# Carriage_Board.net
KiCad netlist of a schematic drawn in EAGLE
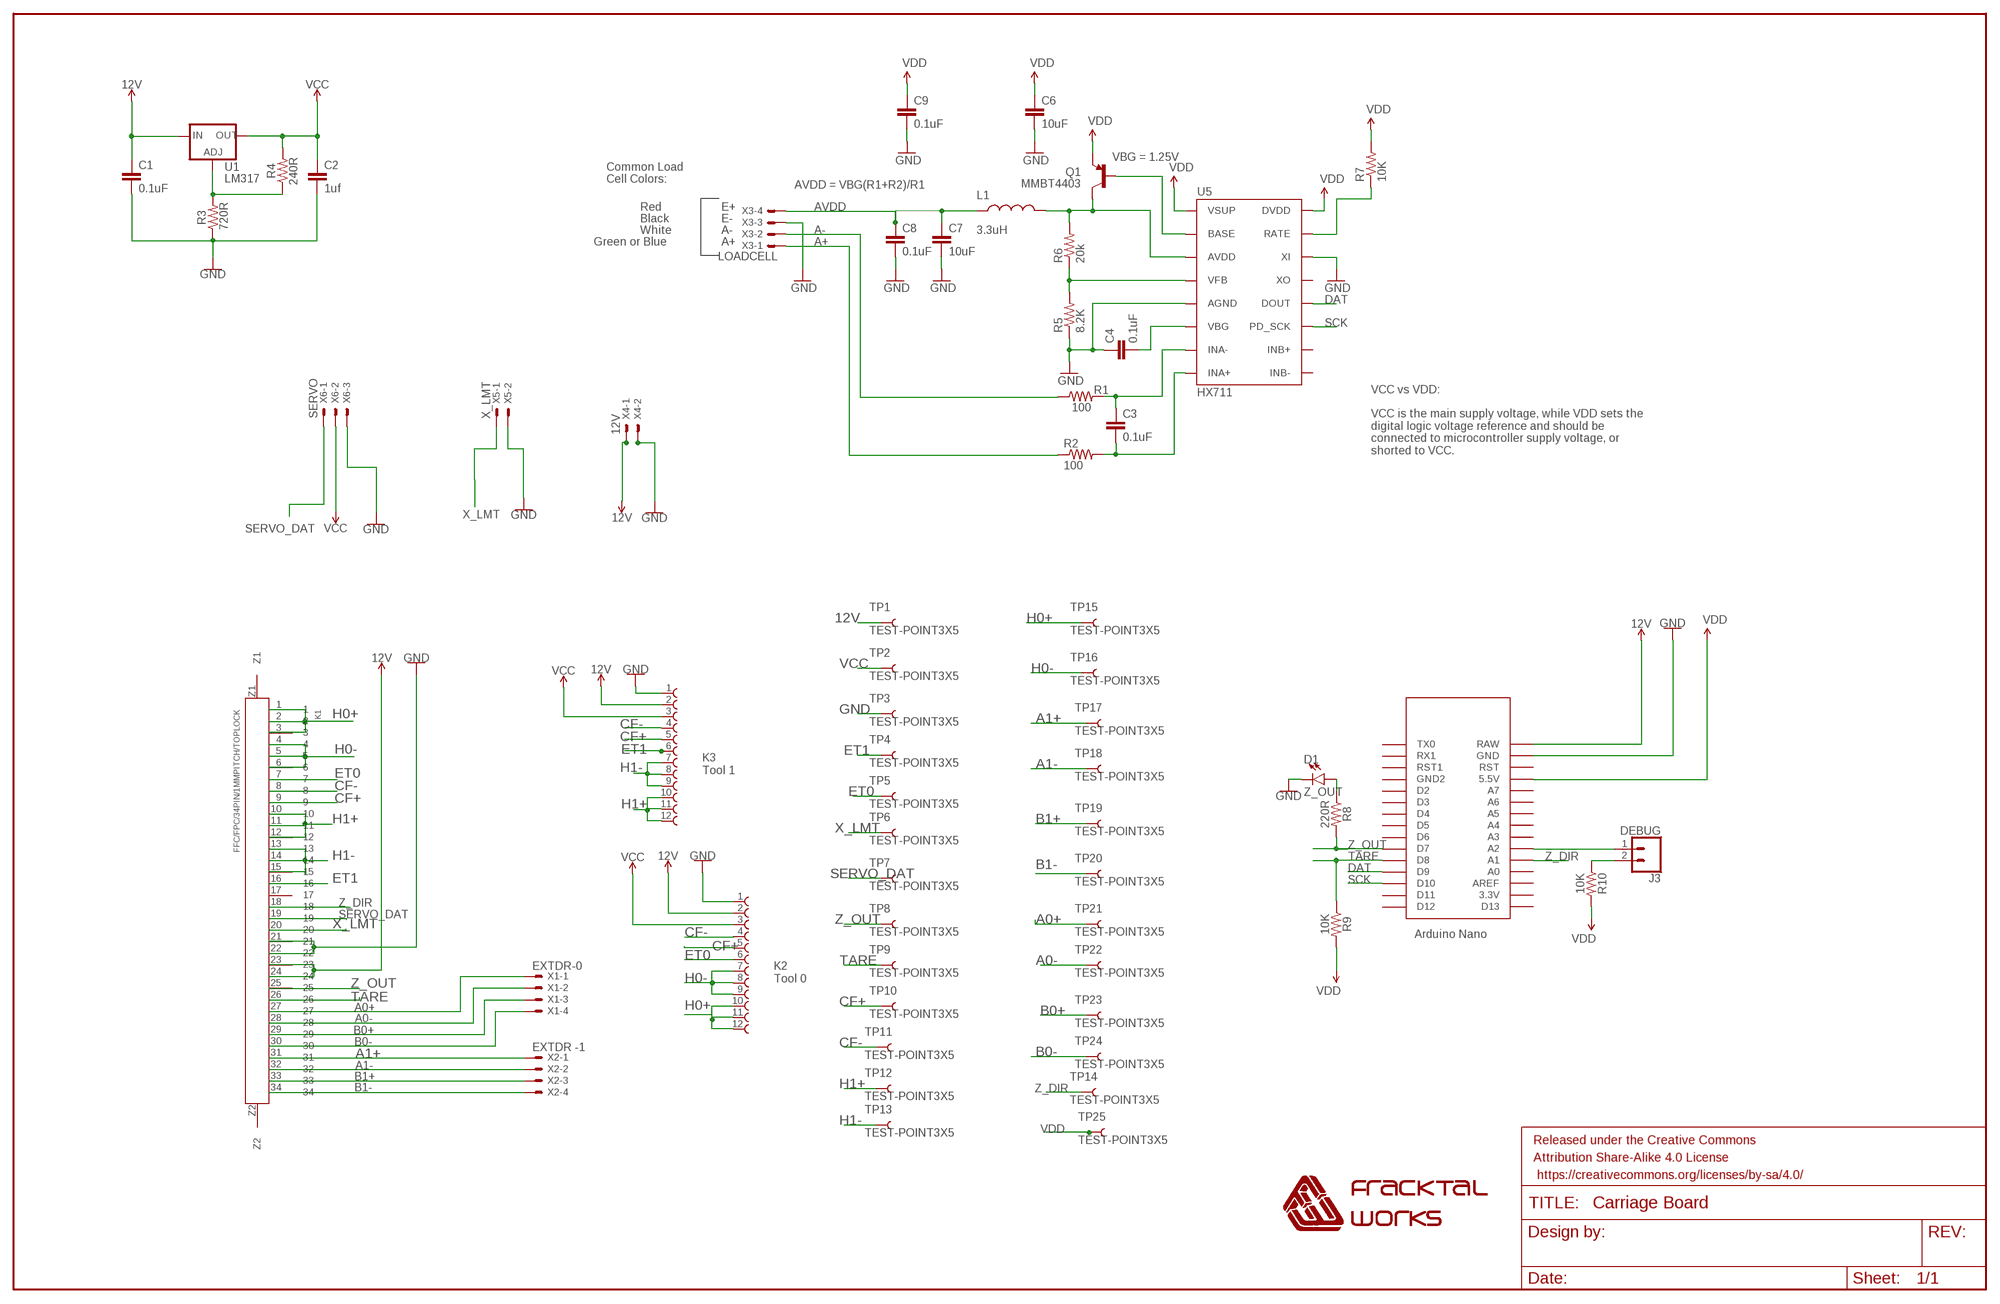
[diagram p0: schematic, sheet 1]

(export (version "E")
  (design (tool "Eeschema 10.0.6"))
  (components
    (comp (ref "C1")
      (value "0.1uF")
      (footprint "eagle-import:0603")
      (libsource (lib "eagle-import") (part "9.0PF-0603-50V-10%"))
    )
    (comp (ref "C2")
      (value "1uf")
      (footprint "eagle-import:0603")
      (libsource (lib "eagle-import") (part "9.0PF-0603-50V-10%"))
    )
    (comp (ref "C3")
      (value "0.1uF")
      (footprint "eagle-import:0603-CAP")
      (libsource (lib "eagle-import") (part "0.1UF-25V-5%(0603)"))
    )
    (comp (ref "C4")
      (value "0.1uF")
      (footprint "eagle-import:0603-CAP")
      (libsource (lib "eagle-import") (part "0.1UF-25V-5%(0603)"))
    )
    (comp (ref "C6")
      (value "10uF")
      (footprint "eagle-import:1210")
      (libsource (lib "eagle-import") (part "10UF50V20%(1210)"))
    )
    (comp (ref "C7")
      (value "10uF")
      (footprint "eagle-import:1210")
      (libsource (lib "eagle-import") (part "10UF50V20%(1210)"))
    )
    (comp (ref "C8")
      (value "0.1uF")
      (footprint "eagle-import:0603-CAP")
      (libsource (lib "eagle-import") (part "0.1UF-25V-5%(0603)"))
    )
    (comp (ref "C9")
      (value "0.1uF")
      (footprint "eagle-import:0603-CAP")
      (libsource (lib "eagle-import") (part "0.1UF-25V-5%(0603)"))
    )
    (comp (ref "D1")
      (value "Z_OUT")
      (footprint "eagle-import:LED_3MM")
      (libsource (lib "eagle-import") (part "LED3MM"))
    )
    (comp (ref "FRAME1")
      (value "FRAME-LEDGER")
      (footprint "eagle-import:CREATIVE_COMMONS")
      (libsource (lib "eagle-import") (part "FRAME-LEDGER"))
    )
    (comp (ref "J3")
      (value "DEBUG")
      (footprint "eagle-import:1X02")
      (libsource (lib "eagle-import") (part "CONN_02"))
    )
    (comp (ref "K1")
      (value "FFC/FPC/34PIN/1MMPITCH/TOPLOCK")
      (footprint "eagle-import:34PIN_1MMPITCH_FFC_FPC")
      (libsource (lib "eagle-import") (part "FFC/FPC/34PIN/1MMPITCH/TOPLOCK"))
    )
    (comp (ref "K2")
      (value "Tool 0")
      (footprint "eagle-import:68611214122")
      (libsource (lib "eagle-import") (part "68611214122"))
    )
    (comp (ref "K3")
      (value "Tool 1")
      (footprint "eagle-import:68611214122")
      (libsource (lib "eagle-import") (part "68611214122"))
    )
    (comp (ref "L1")
      (value "3.3uH")
      (footprint "eagle-import:0805")
      (libsource (lib "eagle-import") (part "INDUCTOR0805-IND"))
    )
    (comp (ref "Q1")
      (value "MMBT4403")
      (footprint "eagle-import:SOT23-3")
      (libsource (lib "eagle-import") (part "TRANSISTOR_PNPMMBT4403"))
    )
    (comp (ref "R1")
      (value "100")
      (footprint "eagle-import:0603-RES")
      (libsource (lib "eagle-import") (part "100OHM-1/10W-1%(0603)"))
    )
    (comp (ref "R2")
      (value "100")
      (footprint "eagle-import:0603-RES")
      (libsource (lib "eagle-import") (part "100OHM-1/10W-1%(0603)"))
    )
    (comp (ref "R3")
      (value "720R")
      (footprint "eagle-import:0603")
      (libsource (lib "eagle-import") (part "RESISTOR0603"))
    )
    (comp (ref "R4")
      (value "240R")
      (footprint "eagle-import:0603")
      (libsource (lib "eagle-import") (part "RESISTOR0603"))
    )
    (comp (ref "R5")
      (value "8.2K")
      (footprint "eagle-import:0603-RES")
      (libsource (lib "eagle-import") (part "8.2KOHM-1/10W-5%(0603)"))
    )
    (comp (ref "R6")
      (value "20k")
      (footprint "eagle-import:0603-RES")
      (libsource (lib "eagle-import") (part "20KOHM1/10W1%(0603)"))
    )
    (comp (ref "R7")
      (value "10K")
      (footprint "eagle-import:0603-RES")
      (libsource (lib "eagle-import") (part "10KOHM-1/10W-1%(0603)0603"))
    )
    (comp (ref "R8")
      (value "220R")
      (footprint "eagle-import:0603")
      (libsource (lib "eagle-import") (part "RESISTOR0603"))
    )
    (comp (ref "R9")
      (value "10K")
      (footprint "eagle-import:0603")
      (libsource (lib "eagle-import") (part "RESISTOR0603"))
    )
    (comp (ref "R10")
      (value "10K")
      (footprint "eagle-import:0603")
      (libsource (lib "eagle-import") (part "RESISTOR0603"))
    )
    (comp (ref "TP1")
      (value "TEST-POINT3X5")
      (footprint "eagle-import:PAD.03X.05")
      (libsource (lib "eagle-import") (part "TEST-POINT3X5"))
    )
    (comp (ref "TP2")
      (value "TEST-POINT3X5")
      (footprint "eagle-import:PAD.03X.05")
      (libsource (lib "eagle-import") (part "TEST-POINT3X5"))
    )
    (comp (ref "TP3")
      (value "TEST-POINT3X5")
      (footprint "eagle-import:PAD.03X.05")
      (libsource (lib "eagle-import") (part "TEST-POINT3X5"))
    )
    (comp (ref "TP4")
      (value "TEST-POINT3X5")
      (footprint "eagle-import:PAD.03X.05")
      (libsource (lib "eagle-import") (part "TEST-POINT3X5"))
    )
    (comp (ref "TP5")
      (value "TEST-POINT3X5")
      (footprint "eagle-import:PAD.03X.05")
      (libsource (lib "eagle-import") (part "TEST-POINT3X5"))
    )
    (comp (ref "TP6")
      (value "TEST-POINT3X5")
      (footprint "eagle-import:PAD.03X.05")
      (libsource (lib "eagle-import") (part "TEST-POINT3X5"))
    )
    (comp (ref "TP7")
      (value "TEST-POINT3X5")
      (footprint "eagle-import:PAD.03X.05")
      (libsource (lib "eagle-import") (part "TEST-POINT3X5"))
    )
    (comp (ref "TP8")
      (value "TEST-POINT3X5")
      (footprint "eagle-import:PAD.03X.05")
      (libsource (lib "eagle-import") (part "TEST-POINT3X5"))
    )
    (comp (ref "TP9")
      (value "TEST-POINT3X5")
      (footprint "eagle-import:PAD.03X.05")
      (libsource (lib "eagle-import") (part "TEST-POINT3X5"))
    )
    (comp (ref "TP10")
      (value "TEST-POINT3X5")
      (footprint "eagle-import:PAD.03X.05")
      (libsource (lib "eagle-import") (part "TEST-POINT3X5"))
    )
    (comp (ref "TP11")
      (value "TEST-POINT3X5")
      (footprint "eagle-import:PAD.03X.05")
      (libsource (lib "eagle-import") (part "TEST-POINT3X5"))
    )
    (comp (ref "TP12")
      (value "TEST-POINT3X5")
      (footprint "eagle-import:PAD.03X.05")
      (libsource (lib "eagle-import") (part "TEST-POINT3X5"))
    )
    (comp (ref "TP13")
      (value "TEST-POINT3X5")
      (footprint "eagle-import:PAD.03X.05")
      (libsource (lib "eagle-import") (part "TEST-POINT3X5"))
    )
    (comp (ref "TP14")
      (value "TEST-POINT3X5")
      (footprint "eagle-import:PAD.03X.05")
      (libsource (lib "eagle-import") (part "TEST-POINT3X5"))
    )
    (comp (ref "TP15")
      (value "TEST-POINT3X5")
      (footprint "eagle-import:PAD.03X.05")
      (libsource (lib "eagle-import") (part "TEST-POINT3X5"))
    )
    (comp (ref "TP16")
      (value "TEST-POINT3X5")
      (footprint "eagle-import:PAD.03X.05")
      (libsource (lib "eagle-import") (part "TEST-POINT3X5"))
    )
    (comp (ref "TP17")
      (value "TEST-POINT3X5")
      (footprint "eagle-import:PAD.03X.05")
      (libsource (lib "eagle-import") (part "TEST-POINT3X5"))
    )
    (comp (ref "TP18")
      (value "TEST-POINT3X5")
      (footprint "eagle-import:PAD.03X.05")
      (libsource (lib "eagle-import") (part "TEST-POINT3X5"))
    )
    (comp (ref "TP19")
      (value "TEST-POINT3X5")
      (footprint "eagle-import:PAD.03X.05")
      (libsource (lib "eagle-import") (part "TEST-POINT3X5"))
    )
    (comp (ref "TP20")
      (value "TEST-POINT3X5")
      (footprint "eagle-import:PAD.03X.05")
      (libsource (lib "eagle-import") (part "TEST-POINT3X5"))
    )
    (comp (ref "TP21")
      (value "TEST-POINT3X5")
      (footprint "eagle-import:PAD.03X.05")
      (libsource (lib "eagle-import") (part "TEST-POINT3X5"))
    )
    (comp (ref "TP22")
      (value "TEST-POINT3X5")
      (footprint "eagle-import:PAD.03X.05")
      (libsource (lib "eagle-import") (part "TEST-POINT3X5"))
    )
    (comp (ref "TP23")
      (value "TEST-POINT3X5")
      (footprint "eagle-import:PAD.03X.05")
      (libsource (lib "eagle-import") (part "TEST-POINT3X5"))
    )
    (comp (ref "TP24")
      (value "TEST-POINT3X5")
      (footprint "eagle-import:PAD.03X.05")
      (libsource (lib "eagle-import") (part "TEST-POINT3X5"))
    )
    (comp (ref "TP25")
      (value "TEST-POINT3X5")
      (footprint "eagle-import:PAD.03X.05")
      (libsource (lib "eagle-import") (part "TEST-POINT3X5"))
    )
    (comp (ref "U$1")
      (value "NANO")
      (footprint "eagle-import:NANO")
      (libsource (lib "eagle-import") (part "NANO"))
    )
    (comp (ref "U$2")
      (value "FWLOGO")
      (footprint "eagle-import:FWLOGO")
      (libsource (lib "eagle-import") (part "FWLOGO"))
    )
    (comp (ref "U1")
      (value "LM317")
      (footprint "eagle-import:SOT223")
      (libsource (lib "eagle-import") (part "V_REG_317SMD"))
    )
    (comp (ref "U5")
      (value "HX711")
      (footprint "eagle-import:SO16")
      (libsource (lib "eagle-import") (part "HX711HX711"))
    )
    (comp (ref "X1")
      (value "EXTDR-0")
      (footprint "eagle-import:JST-XH-04-PACKAGE-LONG-PAD")
      (libsource (lib "eagle-import") (part "JST-XH-04-PIN-LONG-PAD"))
    )
    (comp (ref "X2")
      (value "EXTDR -1")
      (footprint "eagle-import:JST-XH-04-PACKAGE-LONG-PAD")
      (libsource (lib "eagle-import") (part "JST-XH-04-PIN-LONG-PAD"))
    )
    (comp (ref "X3")
      (value "LOADCELL")
      (footprint "eagle-import:JST-XH-04-PACKAGE-LONG-PAD")
      (libsource (lib "eagle-import") (part "JST-XH-04-PIN-LONG-PAD"))
    )
    (comp (ref "X4")
      (value "12V")
      (footprint "eagle-import:JST-XH-02-PACKAGE-LONG-PAD")
      (libsource (lib "eagle-import") (part "JST-XH-02-PIN-LONG-PAD"))
    )
    (comp (ref "X5")
      (value "X_LMT")
      (footprint "eagle-import:JST-XH-02-PACKAGE-LONG-PAD")
      (libsource (lib "eagle-import") (part "JST-XH-02-PIN-LONG-PAD"))
    )
    (comp (ref "X6")
      (value "SERVO")
      (footprint "eagle-import:JST-XH-03-PACKAGE-LONG-PAD")
      (libsource (lib "eagle-import") (part "JST-XH-03-PIN-LONG-PAD"))
    )
  )
  (nets
    (net (code "1") (name "/A+") (class "Default")
      (node (ref "R2") (pin "1") (pinfunction "1_1") (pintype "passive"))
      (node (ref "X3") (pin "1") (pinfunction "S_1") (pintype "passive"))
    )
    (net (code "2") (name "/A-") (class "Default")
      (node (ref "R1") (pin "1") (pinfunction "1_1") (pintype "passive"))
      (node (ref "X3") (pin "2") (pinfunction "S_2") (pintype "passive"))
    )
    (net (code "3") (name "/A0+") (class "Default")
      (node (ref "K1") (pin "27") (pinfunction "27_27") (pintype "bidirectional"))
      (node (ref "TP21") (pin "P$1") (pinfunction "1_P$1") (pintype "bidirectional"))
      (node (ref "X1") (pin "1") (pinfunction "S_1") (pintype "passive"))
    )
    (net (code "4") (name "/A0-") (class "Default")
      (node (ref "K1") (pin "28") (pinfunction "28_28") (pintype "bidirectional"))
      (node (ref "TP22") (pin "P$1") (pinfunction "1_P$1") (pintype "bidirectional"))
      (node (ref "X1") (pin "2") (pinfunction "S_2") (pintype "passive"))
    )
    (net (code "5") (name "/A1+") (class "Default")
      (node (ref "K1") (pin "31") (pinfunction "31_31") (pintype "bidirectional"))
      (node (ref "TP17") (pin "P$1") (pinfunction "1_P$1") (pintype "bidirectional"))
      (node (ref "X2") (pin "1") (pinfunction "S_1") (pintype "passive"))
    )
    (net (code "6") (name "/A1-") (class "Default")
      (node (ref "K1") (pin "32") (pinfunction "32_32") (pintype "bidirectional"))
      (node (ref "TP18") (pin "P$1") (pinfunction "1_P$1") (pintype "bidirectional"))
      (node (ref "X2") (pin "2") (pinfunction "S_2") (pintype "passive"))
    )
    (net (code "7") (name "/AVDD") (class "Default")
      (node (ref "C7") (pin "1") (pinfunction "1_1") (pintype "passive"))
      (node (ref "C8") (pin "1") (pinfunction "1_1") (pintype "passive"))
      (node (ref "L1") (pin "1") (pinfunction "1_1") (pintype "passive"))
      (node (ref "X3") (pin "4") (pinfunction "S_4") (pintype "passive"))
    )
    (net (code "8") (name "/B0+") (class "Default")
      (node (ref "K1") (pin "29") (pinfunction "29_29") (pintype "bidirectional"))
      (node (ref "TP23") (pin "P$1") (pinfunction "1_P$1") (pintype "bidirectional"))
      (node (ref "X1") (pin "3") (pinfunction "S_3") (pintype "passive"))
    )
    (net (code "9") (name "/B0-") (class "Default")
      (node (ref "K1") (pin "30") (pinfunction "30_30") (pintype "bidirectional"))
      (node (ref "TP24") (pin "P$1") (pinfunction "1_P$1") (pintype "bidirectional"))
      (node (ref "X1") (pin "4") (pinfunction "S_4") (pintype "passive"))
    )
    (net (code "10") (name "/B1+") (class "Default")
      (node (ref "K1") (pin "33") (pinfunction "33_33") (pintype "bidirectional"))
      (node (ref "TP19") (pin "P$1") (pinfunction "1_P$1") (pintype "bidirectional"))
      (node (ref "X2") (pin "3") (pinfunction "S_3") (pintype "passive"))
    )
    (net (code "11") (name "/B1-") (class "Default")
      (node (ref "K1") (pin "34") (pinfunction "34_34") (pintype "bidirectional"))
      (node (ref "TP20") (pin "P$1") (pinfunction "1_P$1") (pintype "bidirectional"))
      (node (ref "X2") (pin "4") (pinfunction "S_4") (pintype "passive"))
    )
    (net (code "12") (name "/CF+") (class "Default")
      (node (ref "K1") (pin "9") (pinfunction "9_9") (pintype "bidirectional"))
      (node (ref "K2") (pin "5") (pinfunction "5_5") (pintype "passive"))
      (node (ref "K3") (pin "5") (pinfunction "5_5") (pintype "passive"))
      (node (ref "TP10") (pin "P$1") (pinfunction "1_P$1") (pintype "bidirectional"))
    )
    (net (code "13") (name "/CF-") (class "Default")
      (node (ref "K1") (pin "8") (pinfunction "8_8") (pintype "bidirectional"))
      (node (ref "K2") (pin "4") (pinfunction "4_4") (pintype "passive"))
      (node (ref "K3") (pin "4") (pinfunction "4_4") (pintype "passive"))
      (node (ref "TP11") (pin "P$1") (pinfunction "1_P$1") (pintype "bidirectional"))
    )
    (net (code "14") (name "/DAT") (class "Default")
      (node (ref "U$1") (pin "D9") (pinfunction "D9_D9") (pintype "bidirectional"))
      (node (ref "U5") (pin "12") (pinfunction "DOUT_12") (pintype "bidirectional"))
    )
    (net (code "15") (name "/ET0") (class "Default")
      (node (ref "K1") (pin "7") (pinfunction "7_7") (pintype "bidirectional"))
      (node (ref "K2") (pin "6") (pinfunction "6_6") (pintype "passive"))
      (node (ref "TP5") (pin "P$1") (pinfunction "1_P$1") (pintype "bidirectional"))
    )
    (net (code "16") (name "/ET1") (class "Default")
      (node (ref "K1") (pin "16") (pinfunction "16_16") (pintype "bidirectional"))
      (node (ref "K3") (pin "6") (pinfunction "6_6") (pintype "passive"))
      (node (ref "TP4") (pin "P$1") (pinfunction "1_P$1") (pintype "bidirectional"))
    )
    (net (code "17") (name "/H0+") (class "Default")
      (node (ref "K1") (pin "1") (pinfunction "1_1") (pintype "bidirectional"))
      (node (ref "K1") (pin "2") (pinfunction "2_2") (pintype "bidirectional"))
      (node (ref "K1") (pin "3") (pinfunction "3_3") (pintype "bidirectional"))
      (node (ref "K2") (pin "10") (pinfunction "10_10") (pintype "passive"))
      (node (ref "K2") (pin "11") (pinfunction "11_11") (pintype "passive"))
      (node (ref "K2") (pin "12") (pinfunction "12_12") (pintype "passive"))
      (node (ref "TP15") (pin "P$1") (pinfunction "1_P$1") (pintype "bidirectional"))
    )
    (net (code "18") (name "/H0-") (class "Default")
      (node (ref "K1") (pin "4") (pinfunction "4_4") (pintype "bidirectional"))
      (node (ref "K1") (pin "5") (pinfunction "5_5") (pintype "bidirectional"))
      (node (ref "K1") (pin "6") (pinfunction "6_6") (pintype "bidirectional"))
      (node (ref "K2") (pin "7") (pinfunction "7_7") (pintype "passive"))
      (node (ref "K2") (pin "8") (pinfunction "8_8") (pintype "passive"))
      (node (ref "K2") (pin "9") (pinfunction "9_9") (pintype "passive"))
      (node (ref "TP16") (pin "P$1") (pinfunction "1_P$1") (pintype "bidirectional"))
    )
    (net (code "19") (name "/H1+") (class "Default")
      (node (ref "K1") (pin "10") (pinfunction "10_10") (pintype "bidirectional"))
      (node (ref "K1") (pin "11") (pinfunction "11_11") (pintype "bidirectional"))
      (node (ref "K1") (pin "12") (pinfunction "12_12") (pintype "bidirectional"))
      (node (ref "K3") (pin "10") (pinfunction "10_10") (pintype "passive"))
      (node (ref "K3") (pin "11") (pinfunction "11_11") (pintype "passive"))
      (node (ref "K3") (pin "12") (pinfunction "12_12") (pintype "passive"))
      (node (ref "TP12") (pin "P$1") (pinfunction "1_P$1") (pintype "bidirectional"))
    )
    (net (code "20") (name "/H1-") (class "Default")
      (node (ref "K1") (pin "13") (pinfunction "13_13") (pintype "bidirectional"))
      (node (ref "K1") (pin "14") (pinfunction "14_14") (pintype "bidirectional"))
      (node (ref "K1") (pin "15") (pinfunction "15_15") (pintype "bidirectional"))
      (node (ref "K3") (pin "7") (pinfunction "7_7") (pintype "passive"))
      (node (ref "K3") (pin "8") (pinfunction "8_8") (pintype "passive"))
      (node (ref "K3") (pin "9") (pinfunction "9_9") (pintype "passive"))
      (node (ref "TP13") (pin "P$1") (pinfunction "1_P$1") (pintype "bidirectional"))
    )
    (net (code "21") (name "/SCK") (class "Default")
      (node (ref "U$1") (pin "D10") (pinfunction "D10_D10") (pintype "bidirectional"))
      (node (ref "U5") (pin "11") (pinfunction "PD_SCK_11") (pintype "bidirectional"))
    )
    (net (code "22") (name "/SERVO_DAT") (class "Default")
      (node (ref "K1") (pin "19") (pinfunction "19_19") (pintype "bidirectional"))
      (node (ref "TP7") (pin "P$1") (pinfunction "1_P$1") (pintype "bidirectional"))
      (node (ref "X6") (pin "1") (pinfunction "S_1") (pintype "passive"))
    )
    (net (code "23") (name "/TARE") (class "Default")
      (node (ref "K1") (pin "26") (pinfunction "26_26") (pintype "bidirectional"))
      (node (ref "R9") (pin "1") (pinfunction "1_1") (pintype "passive"))
      (node (ref "TP9") (pin "P$1") (pinfunction "1_P$1") (pintype "bidirectional"))
      (node (ref "U$1") (pin "D8") (pinfunction "D8_D8") (pintype "bidirectional"))
    )
    (net (code "24") (name "/X_LMT") (class "Default")
      (node (ref "K1") (pin "20") (pinfunction "20_20") (pintype "bidirectional"))
      (node (ref "TP6") (pin "P$1") (pinfunction "1_P$1") (pintype "bidirectional"))
      (node (ref "X5") (pin "1") (pinfunction "S_1") (pintype "passive"))
    )
    (net (code "25") (name "/Z_DIR") (class "Default")
      (node (ref "K1") (pin "18") (pinfunction "18_18") (pintype "bidirectional"))
      (node (ref "TP14") (pin "P$1") (pinfunction "1_P$1") (pintype "bidirectional"))
      (node (ref "U$1") (pin "A1") (pinfunction "A1_A1") (pintype "bidirectional"))
    )
    (net (code "26") (name "/Z_OUT") (class "Default")
      (node (ref "K1") (pin "25") (pinfunction "25_25") (pintype "bidirectional"))
      (node (ref "R8") (pin "2") (pinfunction "2_2") (pintype "passive"))
      (node (ref "TP8") (pin "P$1") (pinfunction "1_P$1") (pintype "bidirectional"))
      (node (ref "U$1") (pin "D7") (pinfunction "D7_D7") (pintype "bidirectional"))
    )
    (net (code "27") (name "12V") (class "Default")
      (node (ref "C1") (pin "1") (pinfunction "1_1") (pintype "passive"))
      (node (ref "K1") (pin "23") (pinfunction "23_23") (pintype "bidirectional"))
      (node (ref "K1") (pin "24") (pinfunction "24_24") (pintype "bidirectional"))
      (node (ref "K2") (pin "2") (pinfunction "2_2") (pintype "passive"))
      (node (ref "K3") (pin "2") (pinfunction "2_2") (pintype "passive"))
      (node (ref "TP1") (pin "P$1") (pinfunction "1_P$1") (pintype "bidirectional"))
      (node (ref "U$1") (pin "RAW") (pinfunction "RAW_RAW") (pintype "bidirectional"))
      (node (ref "U1") (pin "3") (pinfunction "IN_3") (pintype "input"))
      (node (ref "X4") (pin "1") (pinfunction "S_1") (pintype "passive"))
    )
    (net (code "28") (name "GND") (class "Default")
      (node (ref "C1") (pin "2") (pinfunction "2_2") (pintype "passive"))
      (node (ref "C2") (pin "2") (pinfunction "2_2") (pintype "passive"))
      (node (ref "C4") (pin "1") (pinfunction "1_1") (pintype "passive"))
      (node (ref "C6") (pin "2") (pinfunction "2_2") (pintype "passive"))
      (node (ref "C7") (pin "2") (pinfunction "2_2") (pintype "passive"))
      (node (ref "C8") (pin "2") (pinfunction "2_2") (pintype "passive"))
      (node (ref "C9") (pin "2") (pinfunction "2_2") (pintype "passive"))
      (node (ref "D1") (pin "K") (pinfunction "C_K") (pintype "passive"))
      (node (ref "K1") (pin "21") (pinfunction "21_21") (pintype "bidirectional"))
      (node (ref "K1") (pin "22") (pinfunction "22_22") (pintype "bidirectional"))
      (node (ref "K2") (pin "1") (pinfunction "1_1") (pintype "passive"))
      (node (ref "K3") (pin "1") (pinfunction "1_1") (pintype "passive"))
      (node (ref "R3") (pin "1") (pinfunction "1_1") (pintype "passive"))
      (node (ref "R5") (pin "1") (pinfunction "1_1") (pintype "passive"))
      (node (ref "TP3") (pin "P$1") (pinfunction "1_P$1") (pintype "bidirectional"))
      (node (ref "U$1") (pin "GND") (pinfunction "GND_GND") (pintype "bidirectional"))
      (node (ref "U5") (pin "14") (pinfunction "XI_14") (pintype "bidirectional"))
      (node (ref "U5") (pin "5") (pinfunction "AGND_5") (pintype "bidirectional"))
      (node (ref "X3") (pin "3") (pinfunction "S_3") (pintype "passive"))
      (node (ref "X4") (pin "2") (pinfunction "S_2") (pintype "passive"))
      (node (ref "X5") (pin "2") (pinfunction "S_2") (pintype "passive"))
      (node (ref "X6") (pin "3") (pinfunction "S_3") (pintype "passive"))
    )
    (net (code "29") (name "Net-(D1-PadA)") (class "Default")
      (node (ref "D1") (pin "A") (pinfunction "A_A") (pintype "passive"))
      (node (ref "R8") (pin "1") (pinfunction "1_1") (pintype "passive"))
    )
    (net (code "30") (name "Net-(J3-Pad1)") (class "Default")
      (node (ref "J3") (pin "1") (pinfunction "1_1") (pintype "passive"))
      (node (ref "U$1") (pin "A2") (pinfunction "A2_A2") (pintype "bidirectional"))
    )
    (net (code "31") (name "Net-(J3-Pad2)") (class "Default")
      (node (ref "J3") (pin "2") (pinfunction "2_2") (pintype "passive"))
      (node (ref "R10") (pin "1") (pinfunction "1_1") (pintype "passive"))
    )
    (net (code "32") (name "Net-(Q1-B)") (class "Default")
      (node (ref "Q1") (pin "1") (pinfunction "B_1") (pintype "passive"))
      (node (ref "U5") (pin "2") (pinfunction "BASE_2") (pintype "bidirectional"))
    )
    (net (code "33") (name "Net-(Q1-C)") (class "Default")
      (node (ref "L1") (pin "2") (pinfunction "2_2") (pintype "passive"))
      (node (ref "Q1") (pin "3") (pinfunction "C_3") (pintype "passive"))
      (node (ref "R6") (pin "2") (pinfunction "2_2") (pintype "passive"))
      (node (ref "U5") (pin "3") (pinfunction "AVDD_3") (pintype "bidirectional"))
    )
    (net (code "34") (name "Net-(U1-ADJ)") (class "Default")
      (node (ref "R3") (pin "2") (pinfunction "2_2") (pintype "passive"))
      (node (ref "R4") (pin "1") (pinfunction "1_1") (pintype "passive"))
      (node (ref "U1") (pin "1") (pinfunction "ADJ_1") (pintype "input"))
    )
    (net (code "35") (name "Net-(U5-INA+)") (class "Default")
      (node (ref "C3") (pin "2") (pinfunction "2_2") (pintype "passive"))
      (node (ref "R2") (pin "2") (pinfunction "2_2") (pintype "passive"))
      (node (ref "U5") (pin "8") (pinfunction "INA+_8") (pintype "bidirectional"))
    )
    (net (code "36") (name "Net-(U5-INA-)") (class "Default")
      (node (ref "C3") (pin "1") (pinfunction "1_1") (pintype "passive"))
      (node (ref "R1") (pin "2") (pinfunction "2_2") (pintype "passive"))
      (node (ref "U5") (pin "7") (pinfunction "INA-_7") (pintype "bidirectional"))
    )
    (net (code "37") (name "Net-(U5-RATE)") (class "Default")
      (node (ref "R7") (pin "1") (pinfunction "1_1") (pintype "passive"))
      (node (ref "U5") (pin "15") (pinfunction "RATE_15") (pintype "bidirectional"))
    )
    (net (code "38") (name "Net-(U5-VBG)") (class "Default")
      (node (ref "C4") (pin "2") (pinfunction "2_2") (pintype "passive"))
      (node (ref "U5") (pin "6") (pinfunction "VBG_6") (pintype "bidirectional"))
    )
    (net (code "39") (name "Net-(U5-VFB)") (class "Default")
      (node (ref "R5") (pin "2") (pinfunction "2_2") (pintype "passive"))
      (node (ref "R6") (pin "1") (pinfunction "1_1") (pintype "passive"))
      (node (ref "U5") (pin "4") (pinfunction "VFB_4") (pintype "bidirectional"))
    )
    (net (code "40") (name "VCC") (class "Default")
      (node (ref "C2") (pin "1") (pinfunction "1_1") (pintype "passive"))
      (node (ref "K2") (pin "3") (pinfunction "3_3") (pintype "passive"))
      (node (ref "K3") (pin "3") (pinfunction "3_3") (pintype "passive"))
      (node (ref "R4") (pin "2") (pinfunction "2_2") (pintype "passive"))
      (node (ref "TP2") (pin "P$1") (pinfunction "1_P$1") (pintype "bidirectional"))
      (node (ref "U1") (pin "2") (pinfunction "OUT_2") (pintype "output"))
      (node (ref "X6") (pin "2") (pinfunction "S_2") (pintype "passive"))
    )
    (net (code "41") (name "VDD") (class "Default")
      (node (ref "C6") (pin "1") (pinfunction "1_1") (pintype "passive"))
      (node (ref "C9") (pin "1") (pinfunction "1_1") (pintype "passive"))
      (node (ref "Q1") (pin "2") (pinfunction "E_2") (pintype "passive"))
      (node (ref "R10") (pin "2") (pinfunction "2_2") (pintype "passive"))
      (node (ref "R7") (pin "2") (pinfunction "2_2") (pintype "passive"))
      (node (ref "R9") (pin "2") (pinfunction "2_2") (pintype "passive"))
      (node (ref "TP25") (pin "P$1") (pinfunction "1_P$1") (pintype "bidirectional"))
      (node (ref "U$1") (pin "5V") (pinfunction "5.5V_5V") (pintype "bidirectional"))
      (node (ref "U5") (pin "1") (pinfunction "VSUP_1") (pintype "bidirectional"))
      (node (ref "U5") (pin "16") (pinfunction "DVDD_16") (pintype "bidirectional"))
    )
    (net (code "42") (name "unconnected-(K1-Pad17)") (class "Default")
      (node (ref "K1") (pin "17") (pinfunction "17_17") (pintype "bidirectional"))
    )
    (net (code "43") (name "unconnected-(K1-PadZ1)") (class "Default")
      (node (ref "K1") (pin "Z1") (pinfunction "Z1_Z1") (pintype "bidirectional"))
    )
    (net (code "44") (name "unconnected-(K1-PadZ2)") (class "Default")
      (node (ref "K1") (pin "Z2") (pinfunction "Z2_Z2") (pintype "bidirectional"))
    )
    (net (code "45") (name "unconnected-(U$1-GND2-PadGND1)") (class "Default")
      (node (ref "U$1") (pin "GND1") (pinfunction "GND2_GND1") (pintype "bidirectional"))
    )
    (net (code "46") (name "unconnected-(U$1-Pad3.3V)") (class "Default")
      (node (ref "U$1") (pin "3.3V") (pinfunction "3.3V_3.3V") (pintype "bidirectional"))
    )
    (net (code "47") (name "unconnected-(U$1-PadA0)") (class "Default")
      (node (ref "U$1") (pin "A0") (pinfunction "A0_A0") (pintype "bidirectional"))
    )
    (net (code "48") (name "unconnected-(U$1-PadA3)") (class "Default")
      (node (ref "U$1") (pin "A3") (pinfunction "A3_A3") (pintype "bidirectional"))
    )
    (net (code "49") (name "unconnected-(U$1-PadA4)") (class "Default")
      (node (ref "U$1") (pin "A4") (pinfunction "A4_A4") (pintype "bidirectional"))
    )
    (net (code "50") (name "unconnected-(U$1-PadA5)") (class "Default")
      (node (ref "U$1") (pin "A5") (pinfunction "A5_A5") (pintype "bidirectional"))
    )
    (net (code "51") (name "unconnected-(U$1-PadA6)") (class "Default")
      (node (ref "U$1") (pin "A6") (pinfunction "A6_A6") (pintype "bidirectional"))
    )
    (net (code "52") (name "unconnected-(U$1-PadA7)") (class "Default")
      (node (ref "U$1") (pin "A7") (pinfunction "A7_A7") (pintype "bidirectional"))
    )
    (net (code "53") (name "unconnected-(U$1-PadAREF)") (class "Default")
      (node (ref "U$1") (pin "AREF") (pinfunction "AREF_AREF") (pintype "bidirectional"))
    )
    (net (code "54") (name "unconnected-(U$1-PadD2)") (class "Default")
      (node (ref "U$1") (pin "D2") (pinfunction "D2_D2") (pintype "bidirectional"))
    )
    (net (code "55") (name "unconnected-(U$1-PadD3)") (class "Default")
      (node (ref "U$1") (pin "D3") (pinfunction "D3_D3") (pintype "bidirectional"))
    )
    (net (code "56") (name "unconnected-(U$1-PadD4)") (class "Default")
      (node (ref "U$1") (pin "D4") (pinfunction "D4_D4") (pintype "bidirectional"))
    )
    (net (code "57") (name "unconnected-(U$1-PadD5)") (class "Default")
      (node (ref "U$1") (pin "D5") (pinfunction "D5_D5") (pintype "bidirectional"))
    )
    (net (code "58") (name "unconnected-(U$1-PadD6)") (class "Default")
      (node (ref "U$1") (pin "D6") (pinfunction "D6_D6") (pintype "bidirectional"))
    )
    (net (code "59") (name "unconnected-(U$1-PadD11)") (class "Default")
      (node (ref "U$1") (pin "D11") (pinfunction "D11_D11") (pintype "bidirectional"))
    )
    (net (code "60") (name "unconnected-(U$1-PadD12)") (class "Default")
      (node (ref "U$1") (pin "D12") (pinfunction "D12_D12") (pintype "bidirectional"))
    )
    (net (code "61") (name "unconnected-(U$1-PadD13)") (class "Default")
      (node (ref "U$1") (pin "D13") (pinfunction "D13_D13") (pintype "bidirectional"))
    )
    (net (code "62") (name "unconnected-(U$1-PadICSP1)") (class "Default")
      (node (ref "U$1") (pin "ICSP1") (pinfunction "ICSP1_ICSP1") (pintype "bidirectional"))
    )
    (net (code "63") (name "unconnected-(U$1-PadICSP2)") (class "Default")
      (node (ref "U$1") (pin "ICSP2") (pinfunction "ICSP2_ICSP2") (pintype "bidirectional"))
    )
    (net (code "64") (name "unconnected-(U$1-PadICSP3)") (class "Default")
      (node (ref "U$1") (pin "ICSP3") (pinfunction "ICSP3_ICSP3") (pintype "bidirectional"))
    )
    (net (code "65") (name "unconnected-(U$1-PadICSP4)") (class "Default")
      (node (ref "U$1") (pin "ICSP4") (pinfunction "ICSP4_ICSP4") (pintype "bidirectional"))
    )
    (net (code "66") (name "unconnected-(U$1-PadICSP5)") (class "Default")
      (node (ref "U$1") (pin "ICSP5") (pinfunction "ICSP5_ICSP5") (pintype "bidirectional"))
    )
    (net (code "67") (name "unconnected-(U$1-PadICSP6)") (class "Default")
      (node (ref "U$1") (pin "ICSP6") (pinfunction "ICSP6_ICSP6") (pintype "bidirectional"))
    )
    (net (code "68") (name "unconnected-(U$1-PadRST)") (class "Default")
      (node (ref "U$1") (pin "RST") (pinfunction "RST_RST") (pintype "bidirectional"))
    )
    (net (code "69") (name "unconnected-(U$1-PadRST1)") (class "Default")
      (node (ref "U$1") (pin "RST1") (pinfunction "RST1_RST1") (pintype "bidirectional"))
    )
    (net (code "70") (name "unconnected-(U$1-PadRX1)") (class "Default")
      (node (ref "U$1") (pin "RX1") (pinfunction "RX1_RX1") (pintype "bidirectional"))
    )
    (net (code "71") (name "unconnected-(U$1-PadTX0)") (class "Default")
      (node (ref "U$1") (pin "TX0") (pinfunction "TX0_TX0") (pintype "bidirectional"))
    )
    (net (code "72") (name "unconnected-(U5-INB+-Pad10)") (class "Default")
      (node (ref "U5") (pin "10") (pinfunction "INB+_10") (pintype "bidirectional"))
    )
    (net (code "73") (name "unconnected-(U5-INB--Pad9)") (class "Default")
      (node (ref "U5") (pin "9") (pinfunction "INB-_9") (pintype "bidirectional"))
    )
    (net (code "74") (name "unconnected-(U5-XO-Pad13)") (class "Default")
      (node (ref "U5") (pin "13") (pinfunction "XO_13") (pintype "bidirectional"))
    )
  )
)
